# 5v.net
KiCad netlist of a schematic drawn in EAGLE
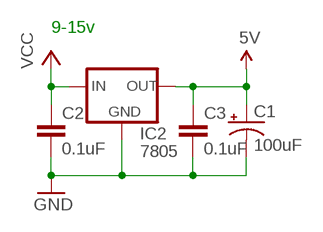
[diagram p0: schematic, sheet 1]

(export (version "E")
  (design (tool "Eeschema 10.0.6"))
  (components
    (comp (ref "C1")
      (value "100uF")
      (footprint "eagle-import:CPOL-RADIAL-100UF-25V")
      (libsource (lib "eagle-import") (part "CAP_POLPTH1"))
    )
    (comp (ref "C2")
      (value "0.1uF")
      (footprint "eagle-import:CAP-PTH-SMALL")
      (libsource (lib "eagle-import") (part "CAPPTH"))
    )
    (comp (ref "C3")
      (value "0.1uF")
      (footprint "eagle-import:CAP-PTH-SMALL")
      (libsource (lib "eagle-import") (part "CAPPTH"))
    )
    (comp (ref "IC2")
      (value "7805")
      (footprint "eagle-import:78XXL")
      (libsource (lib "eagle-import") (part "V_REG_78XXSIDE"))
    )
  )
  (nets
    (net (code "1") (name "5V") (class "Default")
      (node (ref "C1") (pin "1") (pinfunction "+_1") (pintype "passive"))
      (node (ref "C3") (pin "1") (pinfunction "1_1") (pintype "passive"))
      (node (ref "IC2") (pin "OUT") (pinfunction "OUT_OUT") (pintype "output"))
    )
    (net (code "2") (name "GND") (class "Default")
      (node (ref "C1") (pin "2") (pinfunction "-_2") (pintype "passive"))
      (node (ref "C2") (pin "2") (pinfunction "2_2") (pintype "passive"))
      (node (ref "C3") (pin "2") (pinfunction "2_2") (pintype "passive"))
      (node (ref "IC2") (pin "GND") (pinfunction "GND_GND") (pintype "input"))
    )
    (net (code "3") (name "VCC") (class "Default")
      (node (ref "C2") (pin "1") (pinfunction "1_1") (pintype "passive"))
      (node (ref "IC2") (pin "IN") (pinfunction "IN_IN") (pintype "input"))
    )
  )
)
